# SlimPow-CB.net
KiCad netlist of a schematic drawn in EAGLE
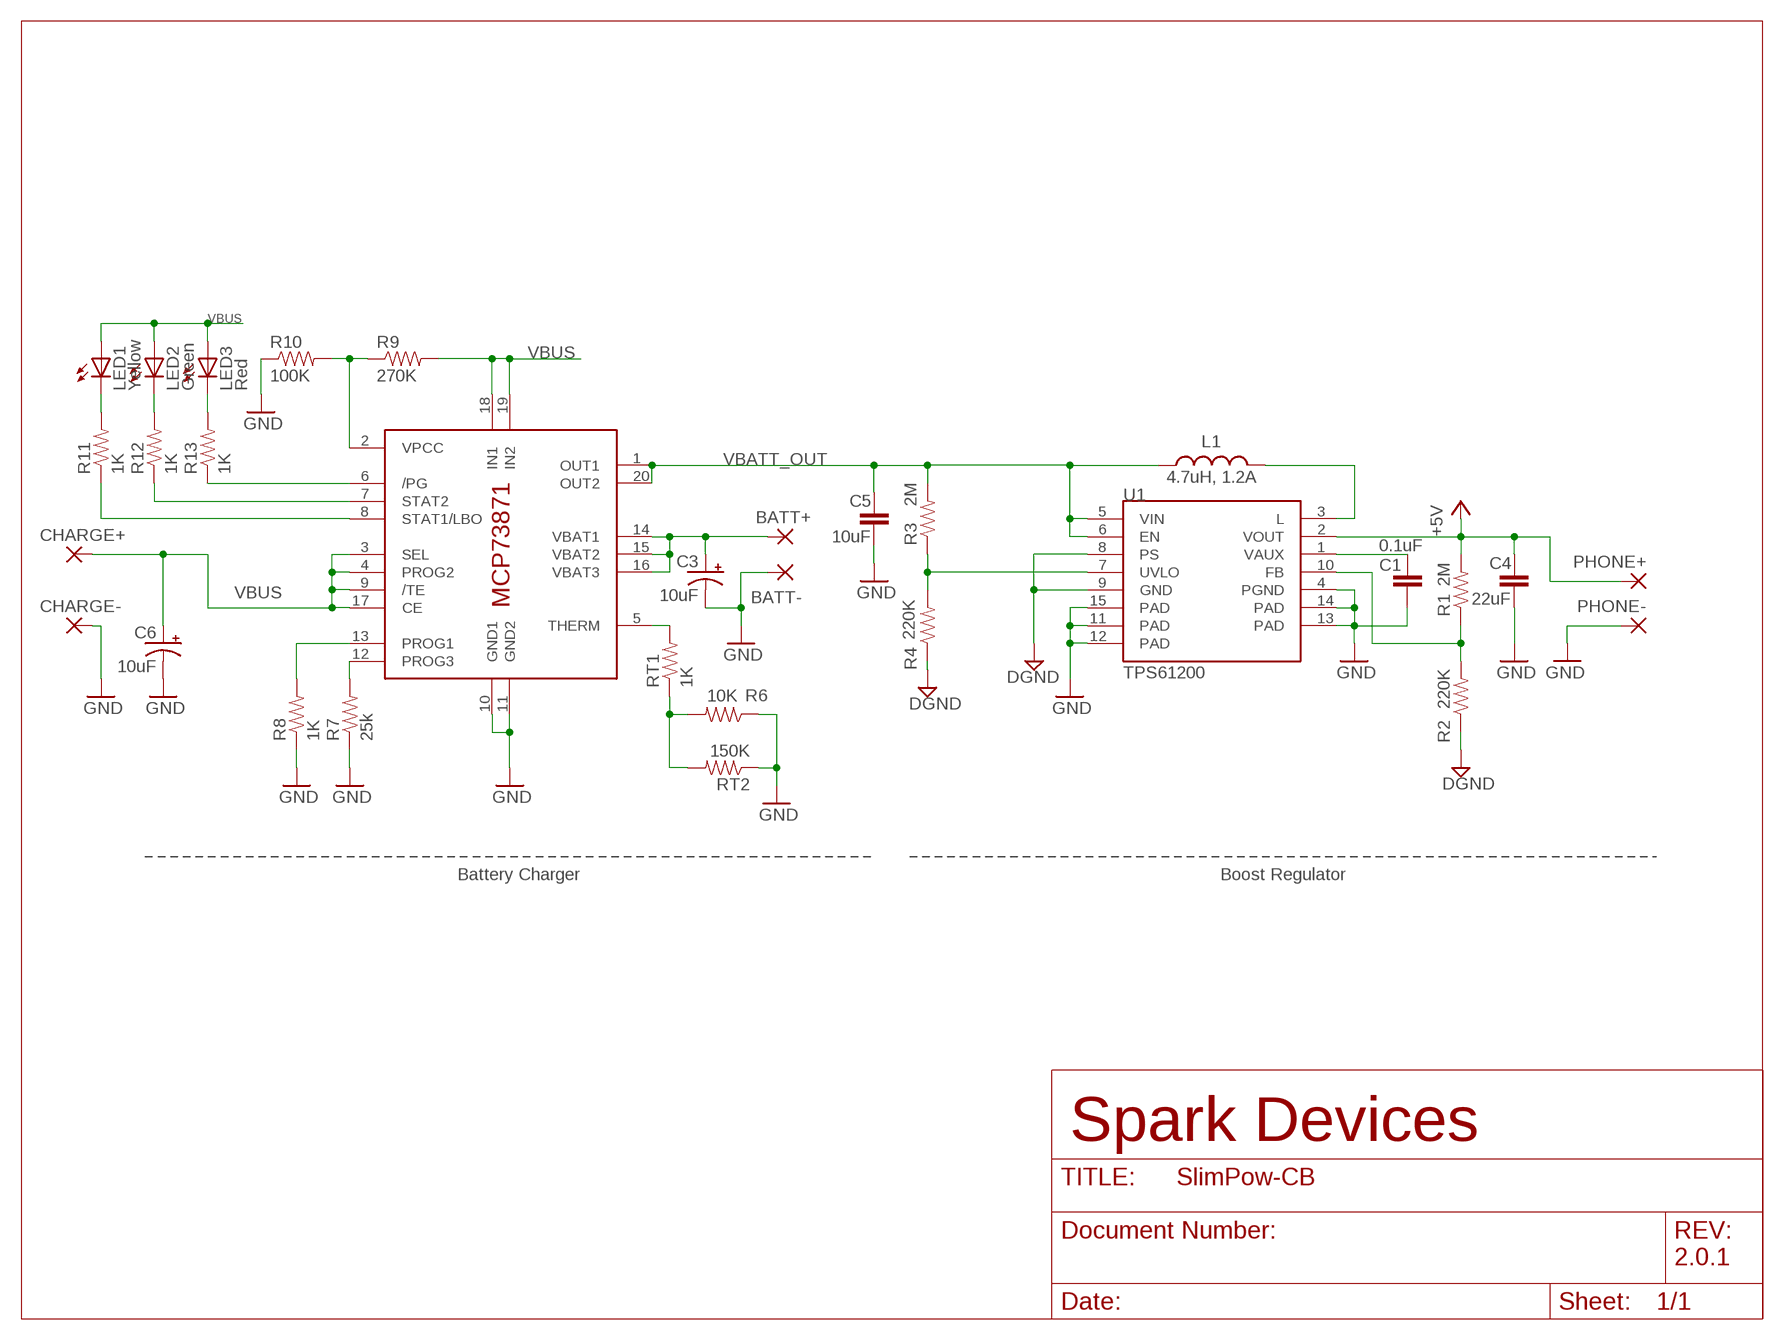
[diagram p0: schematic, sheet 1]

(export (version "E")
  (design (tool "Eeschema 10.0.6"))
  (components
    (comp (ref "BATT+")
      (value "WIREPAD2,15/1,0")
      (footprint "eagle-import:2,15_1,0")
      (libsource (lib "eagle-import") (part "WIREPAD2,15/1,0"))
    )
    (comp (ref "BATT-")
      (value "WIREPAD2,15/1,0")
      (footprint "eagle-import:2,15_1,0")
      (libsource (lib "eagle-import") (part "WIREPAD2,15/1,0"))
    )
    (comp (ref "C1")
      (value "0.1uF")
      (footprint "eagle-import:0402-CAP")
      (libsource (lib "eagle-import") (part "SparkFun-Passives_CAP0402-CAP"))
    )
    (comp (ref "C3")
      (value "10uF")
      (footprint "eagle-import:EIA3216")
      (libsource (lib "eagle-import") (part "10UF-16V-10%(TANT)"))
    )
    (comp (ref "C4")
      (value "22uF")
      (footprint "eagle-import:0805")
      (libsource (lib "eagle-import") (part "SparkFun-Passives_CAP0805"))
    )
    (comp (ref "C5")
      (value "10uF")
      (footprint "eagle-import:1206")
      (libsource (lib "eagle-import") (part "CAP1206"))
    )
    (comp (ref "C6")
      (value "10uF")
      (footprint "eagle-import:EIA3216")
      (fields (field (name "PROD_ID") "CAP-00811"))
      (libsource (lib "eagle-import") (part "10UF-16V-10%(TANT)"))
    )
    (comp (ref "CHARGE+")
      (value "WIREPAD2,15/1,0")
      (footprint "eagle-import:2,15_1,0")
      (libsource (lib "eagle-import") (part "WIREPAD2,15/1,0"))
    )
    (comp (ref "CHARGE-")
      (value "WIREPAD2,15/1,0")
      (footprint "eagle-import:2,15_1,0")
      (libsource (lib "eagle-import") (part "WIREPAD2,15/1,0"))
    )
    (comp (ref "IC1")
      (value "MCP73871")
      (footprint "eagle-import:QFN20")
      (libsource (lib "eagle-import") (part "MCP73871"))
    )
    (comp (ref "L1")
      (value "4.7uH, 1.2A")
      (footprint "eagle-import:CDRH2D09")
      (libsource (lib "eagle-import") (part "INDUCTOR."))
    )
    (comp (ref "LED1")
      (value "Yellow")
      (footprint "eagle-import:LED-0603")
      (libsource (lib "eagle-import") (part "LED0603"))
    )
    (comp (ref "LED2")
      (value "Green")
      (footprint "eagle-import:LED-0603")
      (libsource (lib "eagle-import") (part "LED0603"))
    )
    (comp (ref "LED3")
      (value "Red")
      (footprint "eagle-import:LED-0603")
      (libsource (lib "eagle-import") (part "LED0603"))
    )
    (comp (ref "PHONE+")
      (value "WIREPAD2,15/1,0")
      (footprint "eagle-import:2,15_1,0")
      (libsource (lib "eagle-import") (part "WIREPAD2,15/1,0"))
    )
    (comp (ref "PHONE-")
      (value "WIREPAD2,15/1,0")
      (footprint "eagle-import:2,15_1,0")
      (libsource (lib "eagle-import") (part "WIREPAD2,15/1,0"))
    )
    (comp (ref "R1")
      (value "2M")
      (footprint "eagle-import:0402-RES")
      (libsource (lib "eagle-import") (part "RESISTOR0402-RES"))
    )
    (comp (ref "R2")
      (value "220K")
      (footprint "eagle-import:0402-RES")
      (libsource (lib "eagle-import") (part "RESISTOR0402-RES"))
    )
    (comp (ref "R3")
      (value "2M")
      (footprint "eagle-import:0402-RES")
      (libsource (lib "eagle-import") (part "RESISTOR0402-RES"))
    )
    (comp (ref "R4")
      (value "220K")
      (footprint "eagle-import:0402-RES")
      (libsource (lib "eagle-import") (part "RESISTOR0402-RES"))
    )
    (comp (ref "R6")
      (value "10K")
      (footprint "eagle-import:0402-RES")
      (libsource (lib "eagle-import") (part "RESISTOR0402-RES"))
    )
    (comp (ref "R7")
      (value "25k")
      (footprint "eagle-import:0402-RES")
      (libsource (lib "eagle-import") (part "RESISTOR0402-RES"))
    )
    (comp (ref "R8")
      (value "1K")
      (footprint "eagle-import:0402-RES")
      (libsource (lib "eagle-import") (part "RESISTOR0402-RES"))
    )
    (comp (ref "R9")
      (value "270K")
      (footprint "eagle-import:0402-RES")
      (libsource (lib "eagle-import") (part "RESISTOR0402-RES"))
    )
    (comp (ref "R10")
      (value "100K")
      (footprint "eagle-import:0402-RES")
      (libsource (lib "eagle-import") (part "RESISTOR0402-RES"))
    )
    (comp (ref "R11")
      (value "1K")
      (footprint "eagle-import:0402-RES")
      (libsource (lib "eagle-import") (part "RESISTOR0402-RES"))
    )
    (comp (ref "R12")
      (value "1K")
      (footprint "eagle-import:0402-RES")
      (libsource (lib "eagle-import") (part "RESISTOR0402-RES"))
    )
    (comp (ref "R13")
      (value "1K")
      (footprint "eagle-import:0402-RES")
      (libsource (lib "eagle-import") (part "RESISTOR0402-RES"))
    )
    (comp (ref "RT1")
      (value "1K")
      (footprint "eagle-import:0402-RES")
      (libsource (lib "eagle-import") (part "RESISTOR0402-RES"))
    )
    (comp (ref "RT2")
      (value "150K")
      (footprint "eagle-import:0402-RES")
      (libsource (lib "eagle-import") (part "RESISTOR0402-RES"))
    )
    (comp (ref "U1")
      (value "TPS61200")
      (footprint "eagle-import:QFN-10_PAD")
      (libsource (lib "eagle-import") (part "TPS61200"))
    )
  )
  (nets
    (net (code "1") (name "+5V") (class "Default")
      (node (ref "C4") (pin "1") (pinfunction "1_1") (pintype "passive"))
      (node (ref "PHONE+") (pin "1") (pinfunction "P_1") (pintype "passive"))
      (node (ref "R1") (pin "2") (pinfunction "2_2") (pintype "passive"))
      (node (ref "U1") (pin "2") (pinfunction "VOUT_2") (pintype "passive"))
    )
    (net (code "2") (name "/VBATT_OUT") (class "Default")
      (node (ref "C5") (pin "1") (pinfunction "1_1") (pintype "passive"))
      (node (ref "IC1") (pin "1") (pinfunction "OUT1_1") (pintype "output"))
      (node (ref "IC1") (pin "20") (pinfunction "OUT2_20") (pintype "output"))
      (node (ref "L1") (pin "P$1") (pinfunction "1_P$1") (pintype "passive"))
      (node (ref "R3") (pin "2") (pinfunction "2_2") (pintype "passive"))
      (node (ref "U1") (pin "5") (pinfunction "VIN_5") (pintype "power_in"))
      (node (ref "U1") (pin "6") (pinfunction "EN_6") (pintype "input"))
    )
    (net (code "3") (name "/VBUS") (class "Default")
      (node (ref "C6") (pin "A") (pinfunction "+_A") (pintype "passive"))
      (node (ref "CHARGE+") (pin "1") (pinfunction "P_1") (pintype "passive"))
      (node (ref "IC1") (pin "17") (pinfunction "CE_17") (pintype "input"))
      (node (ref "IC1") (pin "18") (pinfunction "IN1_18") (pintype "input"))
      (node (ref "IC1") (pin "19") (pinfunction "IN2_19") (pintype "input"))
      (node (ref "IC1") (pin "3") (pinfunction "SEL_3") (pintype "input"))
      (node (ref "IC1") (pin "4") (pinfunction "PROG2_4") (pintype "input"))
      (node (ref "IC1") (pin "9") (pinfunction "/TE_9") (pintype "input"))
      (node (ref "LED1") (pin "A") (pinfunction "A_A") (pintype "passive"))
      (node (ref "LED2") (pin "A") (pinfunction "A_A") (pintype "passive"))
      (node (ref "LED3") (pin "A") (pinfunction "A_A") (pintype "passive"))
      (node (ref "R9") (pin "2") (pinfunction "2_2") (pintype "passive"))
    )
    (net (code "4") (name "DGND") (class "Default")
      (node (ref "R2") (pin "1") (pinfunction "1_1") (pintype "passive"))
      (node (ref "R4") (pin "1") (pinfunction "1_1") (pintype "passive"))
      (node (ref "U1") (pin "8") (pinfunction "PS_8") (pintype "input"))
      (node (ref "U1") (pin "9") (pinfunction "GND_9") (pintype "power_in"))
    )
    (net (code "5") (name "GND") (class "Default")
      (node (ref "BATT-") (pin "1") (pinfunction "P_1") (pintype "passive"))
      (node (ref "C1") (pin "2") (pinfunction "2_2") (pintype "passive"))
      (node (ref "C3") (pin "C") (pinfunction "-_C") (pintype "passive"))
      (node (ref "C4") (pin "2") (pinfunction "2_2") (pintype "passive"))
      (node (ref "C5") (pin "2") (pinfunction "2_2") (pintype "passive"))
      (node (ref "C6") (pin "C") (pinfunction "-_C") (pintype "passive"))
      (node (ref "CHARGE-") (pin "1") (pinfunction "P_1") (pintype "passive"))
      (node (ref "IC1") (pin "10") (pinfunction "GND1_10") (pintype "power_in"))
      (node (ref "IC1") (pin "11") (pinfunction "GND2_11") (pintype "power_in"))
      (node (ref "PHONE-") (pin "1") (pinfunction "P_1") (pintype "passive"))
      (node (ref "R10") (pin "1") (pinfunction "1_1") (pintype "passive"))
      (node (ref "R6") (pin "1") (pinfunction "1_1") (pintype "passive"))
      (node (ref "R7") (pin "1") (pinfunction "1_1") (pintype "passive"))
      (node (ref "R8") (pin "1") (pinfunction "1_1") (pintype "passive"))
      (node (ref "RT2") (pin "1") (pinfunction "1_1") (pintype "passive"))
      (node (ref "U1") (pin "11") (pinfunction "PAD_11") (pintype "power_in"))
      (node (ref "U1") (pin "12") (pinfunction "PAD_12") (pintype "power_in"))
      (node (ref "U1") (pin "13") (pinfunction "PAD_13") (pintype "power_in"))
      (node (ref "U1") (pin "14") (pinfunction "PAD_14") (pintype "power_in"))
      (node (ref "U1") (pin "15") (pinfunction "PAD_15") (pintype "power_in"))
      (node (ref "U1") (pin "4") (pinfunction "PGND_4") (pintype "power_in"))
    )
    (net (code "6") (name "Net-(BATT+-P)") (class "Default")
      (node (ref "BATT+") (pin "1") (pinfunction "P_1") (pintype "passive"))
      (node (ref "C3") (pin "A") (pinfunction "+_A") (pintype "passive"))
      (node (ref "IC1") (pin "14") (pinfunction "VBAT1_14") (pintype "output"))
      (node (ref "IC1") (pin "15") (pinfunction "VBAT2_15") (pintype "output"))
      (node (ref "IC1") (pin "16") (pinfunction "VBAT3_16") (pintype "output"))
    )
    (net (code "7") (name "Net-(IC1-PROG1)") (class "Default")
      (node (ref "IC1") (pin "13") (pinfunction "PROG1_13") (pintype "input"))
      (node (ref "R8") (pin "2") (pinfunction "2_2") (pintype "passive"))
    )
    (net (code "8") (name "Net-(IC1-PROG3)") (class "Default")
      (node (ref "IC1") (pin "12") (pinfunction "PROG3_12") (pintype "input"))
      (node (ref "R7") (pin "2") (pinfunction "2_2") (pintype "passive"))
    )
    (net (code "9") (name "Net-(IC1-STAT1{slash}LBO)") (class "Default")
      (node (ref "IC1") (pin "8") (pinfunction "STAT1/LBO_8") (pintype "output"))
      (node (ref "R11") (pin "1") (pinfunction "1_1") (pintype "passive"))
    )
    (net (code "10") (name "Net-(IC1-STAT2)") (class "Default")
      (node (ref "IC1") (pin "7") (pinfunction "STAT2_7") (pintype "output"))
      (node (ref "R12") (pin "1") (pinfunction "1_1") (pintype "passive"))
    )
    (net (code "11") (name "Net-(IC1-THERM)") (class "Default")
      (node (ref "IC1") (pin "5") (pinfunction "THERM_5") (pintype "input"))
      (node (ref "RT1") (pin "2") (pinfunction "2_2") (pintype "passive"))
    )
    (net (code "12") (name "Net-(IC1-VPCC)") (class "Default")
      (node (ref "IC1") (pin "2") (pinfunction "VPCC_2") (pintype "input"))
      (node (ref "R10") (pin "2") (pinfunction "2_2") (pintype "passive"))
      (node (ref "R9") (pin "1") (pinfunction "1_1") (pintype "passive"))
    )
    (net (code "13") (name "Net-(IC1-{slash}PG)") (class "Default")
      (node (ref "IC1") (pin "6") (pinfunction "/PG_6") (pintype "output"))
      (node (ref "R13") (pin "1") (pinfunction "1_1") (pintype "passive"))
    )
    (net (code "14") (name "Net-(L1-2)") (class "Default")
      (node (ref "L1") (pin "P$2") (pinfunction "2_P$2") (pintype "passive"))
      (node (ref "U1") (pin "3") (pinfunction "L_3") (pintype "passive"))
    )
    (net (code "15") (name "Net-(LED1-PadC)") (class "Default")
      (node (ref "LED1") (pin "C") (pinfunction "C_C") (pintype "passive"))
      (node (ref "R11") (pin "2") (pinfunction "2_2") (pintype "passive"))
    )
    (net (code "16") (name "Net-(LED2-PadC)") (class "Default")
      (node (ref "LED2") (pin "C") (pinfunction "C_C") (pintype "passive"))
      (node (ref "R12") (pin "2") (pinfunction "2_2") (pintype "passive"))
    )
    (net (code "17") (name "Net-(LED3-PadC)") (class "Default")
      (node (ref "LED3") (pin "C") (pinfunction "C_C") (pintype "passive"))
      (node (ref "R13") (pin "2") (pinfunction "2_2") (pintype "passive"))
    )
    (net (code "18") (name "Net-(R6-Pad2)") (class "Default")
      (node (ref "R6") (pin "2") (pinfunction "2_2") (pintype "passive"))
      (node (ref "RT1") (pin "1") (pinfunction "1_1") (pintype "passive"))
      (node (ref "RT2") (pin "2") (pinfunction "2_2") (pintype "passive"))
    )
    (net (code "19") (name "Net-(U1-FB)") (class "Default")
      (node (ref "R1") (pin "1") (pinfunction "1_1") (pintype "passive"))
      (node (ref "R2") (pin "2") (pinfunction "2_2") (pintype "passive"))
      (node (ref "U1") (pin "10") (pinfunction "FB_10") (pintype "passive"))
    )
    (net (code "20") (name "Net-(U1-UVLO)") (class "Default")
      (node (ref "R3") (pin "1") (pinfunction "1_1") (pintype "passive"))
      (node (ref "R4") (pin "2") (pinfunction "2_2") (pintype "passive"))
      (node (ref "U1") (pin "7") (pinfunction "UVLO_7") (pintype "passive"))
    )
    (net (code "21") (name "Net-(U1-VAUX)") (class "Default")
      (node (ref "C1") (pin "1") (pinfunction "1_1") (pintype "passive"))
      (node (ref "U1") (pin "1") (pinfunction "VAUX_1") (pintype "passive"))
    )
  )
)
